# Buck_and_Boost_Converters.net
KiCad netlist of a schematic drawn in Altium Designer
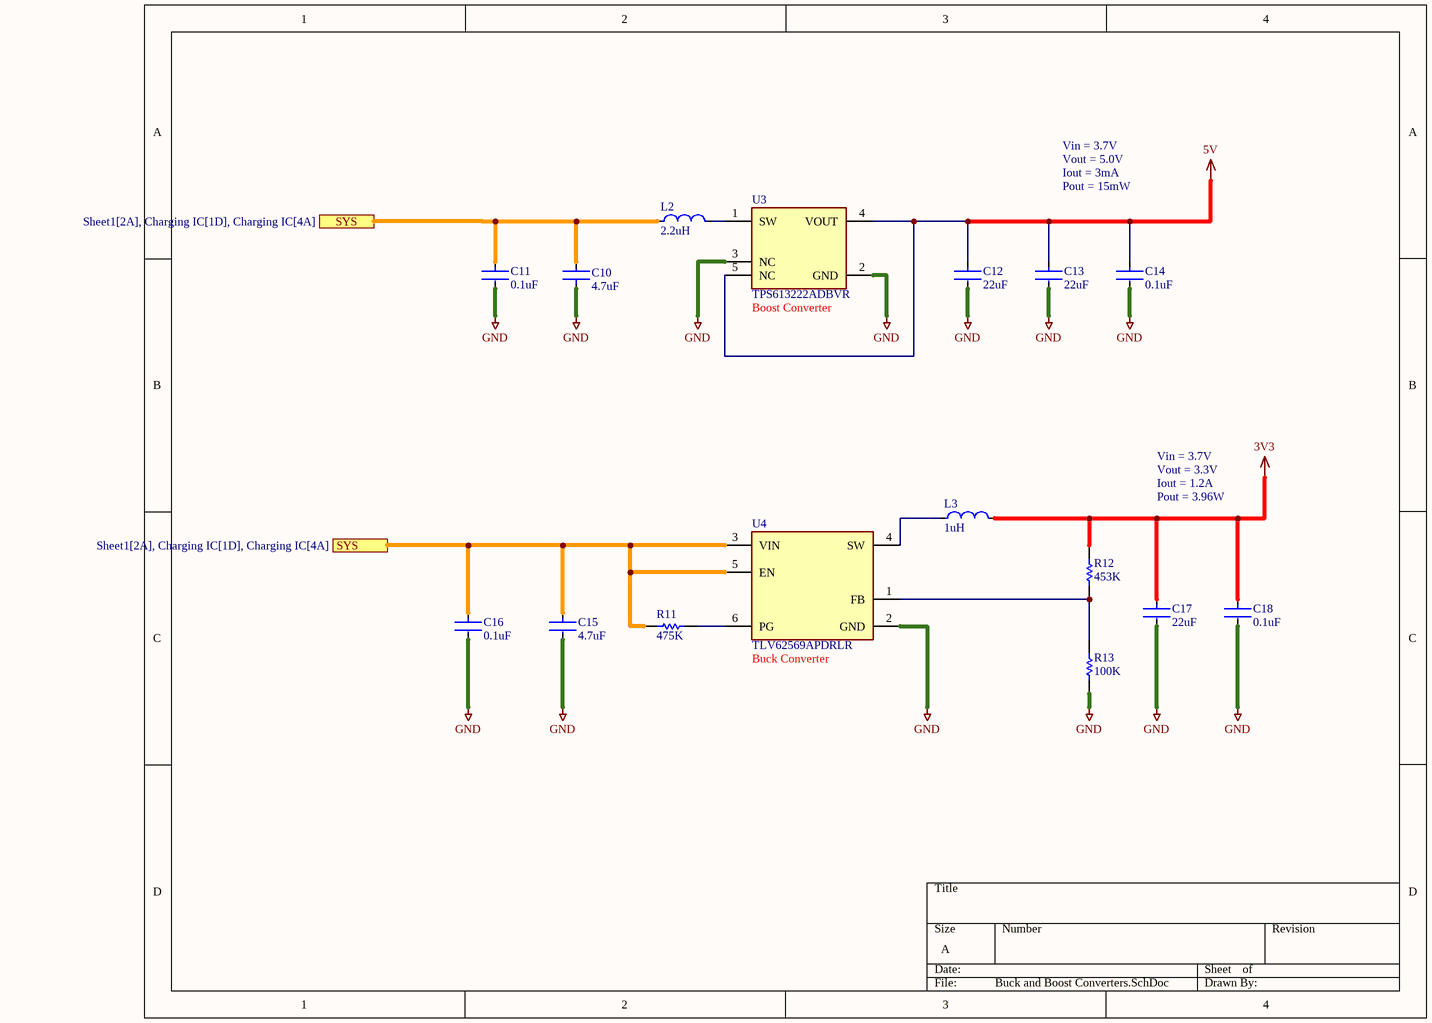
[diagram p0: Buck and Boost Converters.SchDoc]

(export (version "E")
  (design (tool "Eeschema 10.0.6"))
  (components
    (comp (ref "C10")
      (value "4.7uF")
      (footprint "FP-C0603-CG-MFG")
      (description "CAP CER 4.7UF 6.3V X5R 0603")
      (fields (field (name "TOLERANCE") "10%") (field (name "MANUFACTURER") "Kemet"))
      (libsource (lib "Altium Content Vault") (part "11868f565c42a9108669ba33697ecf6"))
    )
    (comp (ref "C11")
      (value "0.1uF")
      (footprint "FP-CC0603-DA-MFG")
      (description "CAP CER 0.1UF 16V X7R 0603")
      (fields
        (field (name "OCTOPART") "https://octopart.com/cc0603krx7r7bb104-yageo-192941")
        (field (name "TOLERANCE") "0.1")
      )
      (libsource (lib "Altium Content Vault") (part "11868f565c42a9108669ba33697ecf6"))
    )
    (comp (ref "C12")
      (value "22uF")
      (footprint "FP-GRM188-0_2-IPC_C")
      (description "Chip Multilayer Ceramic Capacitors for General Purpose, 0603, 22uF, X5R, 15%, 20%, 10V")
      (fields (field (name "TOLERANCE") "20%"))
      (libsource (lib "Altium Content Vault") (part "11868f565c42a9108669ba33697ecf6"))
    )
    (comp (ref "C13")
      (value "22uF")
      (footprint "FP-GRM188-0_2-IPC_C")
      (description "Chip Multilayer Ceramic Capacitors for General Purpose, 0603, 22uF, X5R, 15%, 20%, 10V")
      (fields (field (name "TOLERANCE") "20%"))
      (libsource (lib "Altium Content Vault") (part "11868f565c42a9108669ba33697ecf6"))
    )
    (comp (ref "C14")
      (value "0.1uF")
      (footprint "FP-CC0603-DA-MFG")
      (description "CAP CER 0.1UF 16V X7R 0603")
      (fields
        (field (name "OCTOPART") "https://octopart.com/cc0603krx7r7bb104-yageo-192941")
        (field (name "TOLERANCE") "0.1")
      )
      (libsource (lib "Altium Content Vault") (part "11868f565c42a9108669ba33697ecf6"))
    )
    (comp (ref "C15")
      (value "4.7uF")
      (footprint "FP-C0603-CG-MFG")
      (description "CAP CER 4.7UF 6.3V X5R 0603")
      (fields (field (name "TOLERANCE") "10%") (field (name "MANUFACTURER") "Kemet"))
      (libsource (lib "Altium Content Vault") (part "11868f565c42a9108669ba33697ecf6"))
    )
    (comp (ref "C16")
      (value "0.1uF")
      (footprint "FP-CC0603-DA-MFG")
      (description "CAP CER 0.1UF 16V X7R 0603")
      (fields
        (field (name "OCTOPART") "https://octopart.com/cc0603krx7r7bb104-yageo-192941")
        (field (name "TOLERANCE") "0.1")
      )
      (libsource (lib "Altium Content Vault") (part "11868f565c42a9108669ba33697ecf6"))
    )
    (comp (ref "C17")
      (value "22uF")
      (footprint "FP-GRM188-0_2-IPC_C")
      (description "Chip Multilayer Ceramic Capacitors for General Purpose, 0603, 22uF, X5R, 15%, 20%, 10V")
      (fields (field (name "TOLERANCE") "20%"))
      (libsource (lib "Altium Content Vault") (part "11868f565c42a9108669ba33697ecf6"))
    )
    (comp (ref "C18")
      (value "0.1uF")
      (footprint "FP-CC0603-DA-MFG")
      (description "CAP CER 0.1UF 16V X7R 0603")
      (fields
        (field (name "OCTOPART") "https://octopart.com/cc0603krx7r7bb104-yageo-192941")
        (field (name "TOLERANCE") "0.1")
      )
      (libsource (lib "Altium Content Vault") (part "11868f565c42a9108669ba33697ecf6"))
    )
    (comp (ref "L2")
      (value "2.2uH")
      (footprint "FP-CBMF1608-MFG")
      (description "SMD Inductors 2.2uH ±20% 0.56A 0.221Ω 0603")
      (fields (field (name "TOLERANCE") "20%"))
      (libsource (lib "Altium Content Vault") (part "725321dda6339637d4d059423bc1c3c"))
    )
    (comp (ref "L3")
      (value "1uH")
      (footprint "FP-MLZ1608-MFG")
      (description "FIXED IND 1UH 600MA 150 MOHM SMD")
      (fields (field (name "TOLERANCE") "20%"))
      (libsource (lib "Altium Content Vault") (part "725321dda6339637d4d059423bc1c3c"))
    )
    (comp (ref "R11")
      (value "475K")
      (footprint "RESC1608X55X30LL15T15")
      (fields (field (name "MANUFACTURER") "Panasonic") (field (name "PART NUMBER") "ERJ-3EKF4753V"))
      (libsource (lib "Altium Content Vault") (part "RES"))
    )
    (comp (ref "R12")
      (value "453K")
      (footprint "RESC1608X55X30ML15T15")
      (fields (field (name "MANUFACTURER") "Panasonic") (field (name "PART NUMBER") "ERJ-3EKF4533V"))
      (libsource (lib "Altium Content Vault") (part "RES"))
    )
    (comp (ref "R13")
      (value "100K")
      (footprint "RESC1608X55X30ML20T20")
      (fields (field (name "PART NUMBER") "ERA3AEB104V") (field (name "MANUFACTURER") "Panasonic"))
      (libsource (lib "Altium Content Vault") (part "RES"))
    )
    (comp (ref "U3")
      (value "TPS613222ADBVR")
      (footprint "FP-DBV0005A-MFG")
      (description "IC REG BOOST 5V 2.5A SOT23-5")
      (fields
        (field (name "MANUFACTURER") "Texas Instruments")
        (field (name "OCTOPART") "https://octopart.com/tps613222adbvr-texas+instruments-88135761")
      )
      (libsource (lib "Altium Content Vault") (part "e6940b1ac80ef9322a9cdaeeee8e3a4"))
    )
    (comp (ref "U4")
      (value "TLV62569APDRLR")
      (footprint "FP-DRL0006A-MFG")
      (description "IC REG BUCK ADJ 2A SOT563")
      (libsource (lib "Altium Content Vault") (part "d90e9d6a5f6609701038d1d7d20acc5"))
    )
  )
  (nets
    (net (code "1") (name "/SYS") (class "Default")
      (node (ref "C10") (pin "2") (pinfunction "2_2") (pintype "passive"))
      (node (ref "C11") (pin "1") (pinfunction "1_1") (pintype "passive"))
      (node (ref "C15") (pin "1") (pinfunction "1_1") (pintype "passive"))
      (node (ref "C16") (pin "1") (pinfunction "1_1") (pintype "passive"))
      (node (ref "L2") (pin "1") (pinfunction "1_1") (pintype "passive"))
      (node (ref "R11") (pin "1") (pinfunction "1_1") (pintype "passive"))
      (node (ref "U4") (pin "3") (pinfunction "VIN_3") (pintype "power_in"))
      (node (ref "U4") (pin "5") (pinfunction "EN_5") (pintype "passive"))
    )
    (net (code "2") (name "3V3") (class "Default")
      (node (ref "C17") (pin "1") (pinfunction "1_1") (pintype "passive"))
      (node (ref "C18") (pin "1") (pinfunction "1_1") (pintype "passive"))
      (node (ref "L3") (pin "2") (pinfunction "2_2") (pintype "passive"))
      (node (ref "R12") (pin "2") (pinfunction "2_2") (pintype "passive"))
    )
    (net (code "3") (name "5V") (class "Default")
      (node (ref "C12") (pin "1") (pinfunction "1_1") (pintype "passive"))
      (node (ref "C13") (pin "1") (pinfunction "1_1") (pintype "passive"))
      (node (ref "C14") (pin "1") (pinfunction "1_1") (pintype "passive"))
      (node (ref "U3") (pin "4") (pinfunction "VOUT_4") (pintype "power_in"))
      (node (ref "U3") (pin "5") (pinfunction "NC_5") (pintype "passive"))
    )
    (net (code "4") (name "GND") (class "Default")
      (node (ref "C10") (pin "1") (pinfunction "1_1") (pintype "passive"))
      (node (ref "C11") (pin "2") (pinfunction "2_2") (pintype "passive"))
      (node (ref "C12") (pin "2") (pinfunction "2_2") (pintype "passive"))
      (node (ref "C13") (pin "2") (pinfunction "2_2") (pintype "passive"))
      (node (ref "C14") (pin "2") (pinfunction "2_2") (pintype "passive"))
      (node (ref "C15") (pin "2") (pinfunction "2_2") (pintype "passive"))
      (node (ref "C16") (pin "2") (pinfunction "2_2") (pintype "passive"))
      (node (ref "C17") (pin "2") (pinfunction "2_2") (pintype "passive"))
      (node (ref "C18") (pin "2") (pinfunction "2_2") (pintype "passive"))
      (node (ref "R13") (pin "1") (pinfunction "1_1") (pintype "passive"))
      (node (ref "U3") (pin "2") (pinfunction "GND_2") (pintype "power_in"))
      (node (ref "U3") (pin "3") (pinfunction "NC_3") (pintype "passive"))
      (node (ref "U4") (pin "2") (pinfunction "GND_2") (pintype "power_in"))
    )
    (net (code "5") (name "Net-(U3-SW)") (class "Default")
      (node (ref "L2") (pin "2") (pinfunction "2_2") (pintype "passive"))
      (node (ref "U3") (pin "1") (pinfunction "SW_1") (pintype "power_in"))
    )
    (net (code "6") (name "Net-(U4-FB)") (class "Default")
      (node (ref "R12") (pin "1") (pinfunction "1_1") (pintype "passive"))
      (node (ref "R13") (pin "2") (pinfunction "2_2") (pintype "passive"))
      (node (ref "U4") (pin "1") (pinfunction "FB_1") (pintype "passive"))
    )
    (net (code "7") (name "Net-(U4-PG)") (class "Default")
      (node (ref "R11") (pin "2") (pinfunction "2_2") (pintype "passive"))
      (node (ref "U4") (pin "6") (pinfunction "PG_6") (pintype "open_collector"))
    )
    (net (code "8") (name "Net-(U4-SW)") (class "Default")
      (node (ref "L3") (pin "1") (pinfunction "1_1") (pintype "passive"))
      (node (ref "U4") (pin "4") (pinfunction "SW_4") (pintype "passive"))
    )
  )
)
